# interface_01.net
KiCad netlist of a schematic drawn in EAGLE
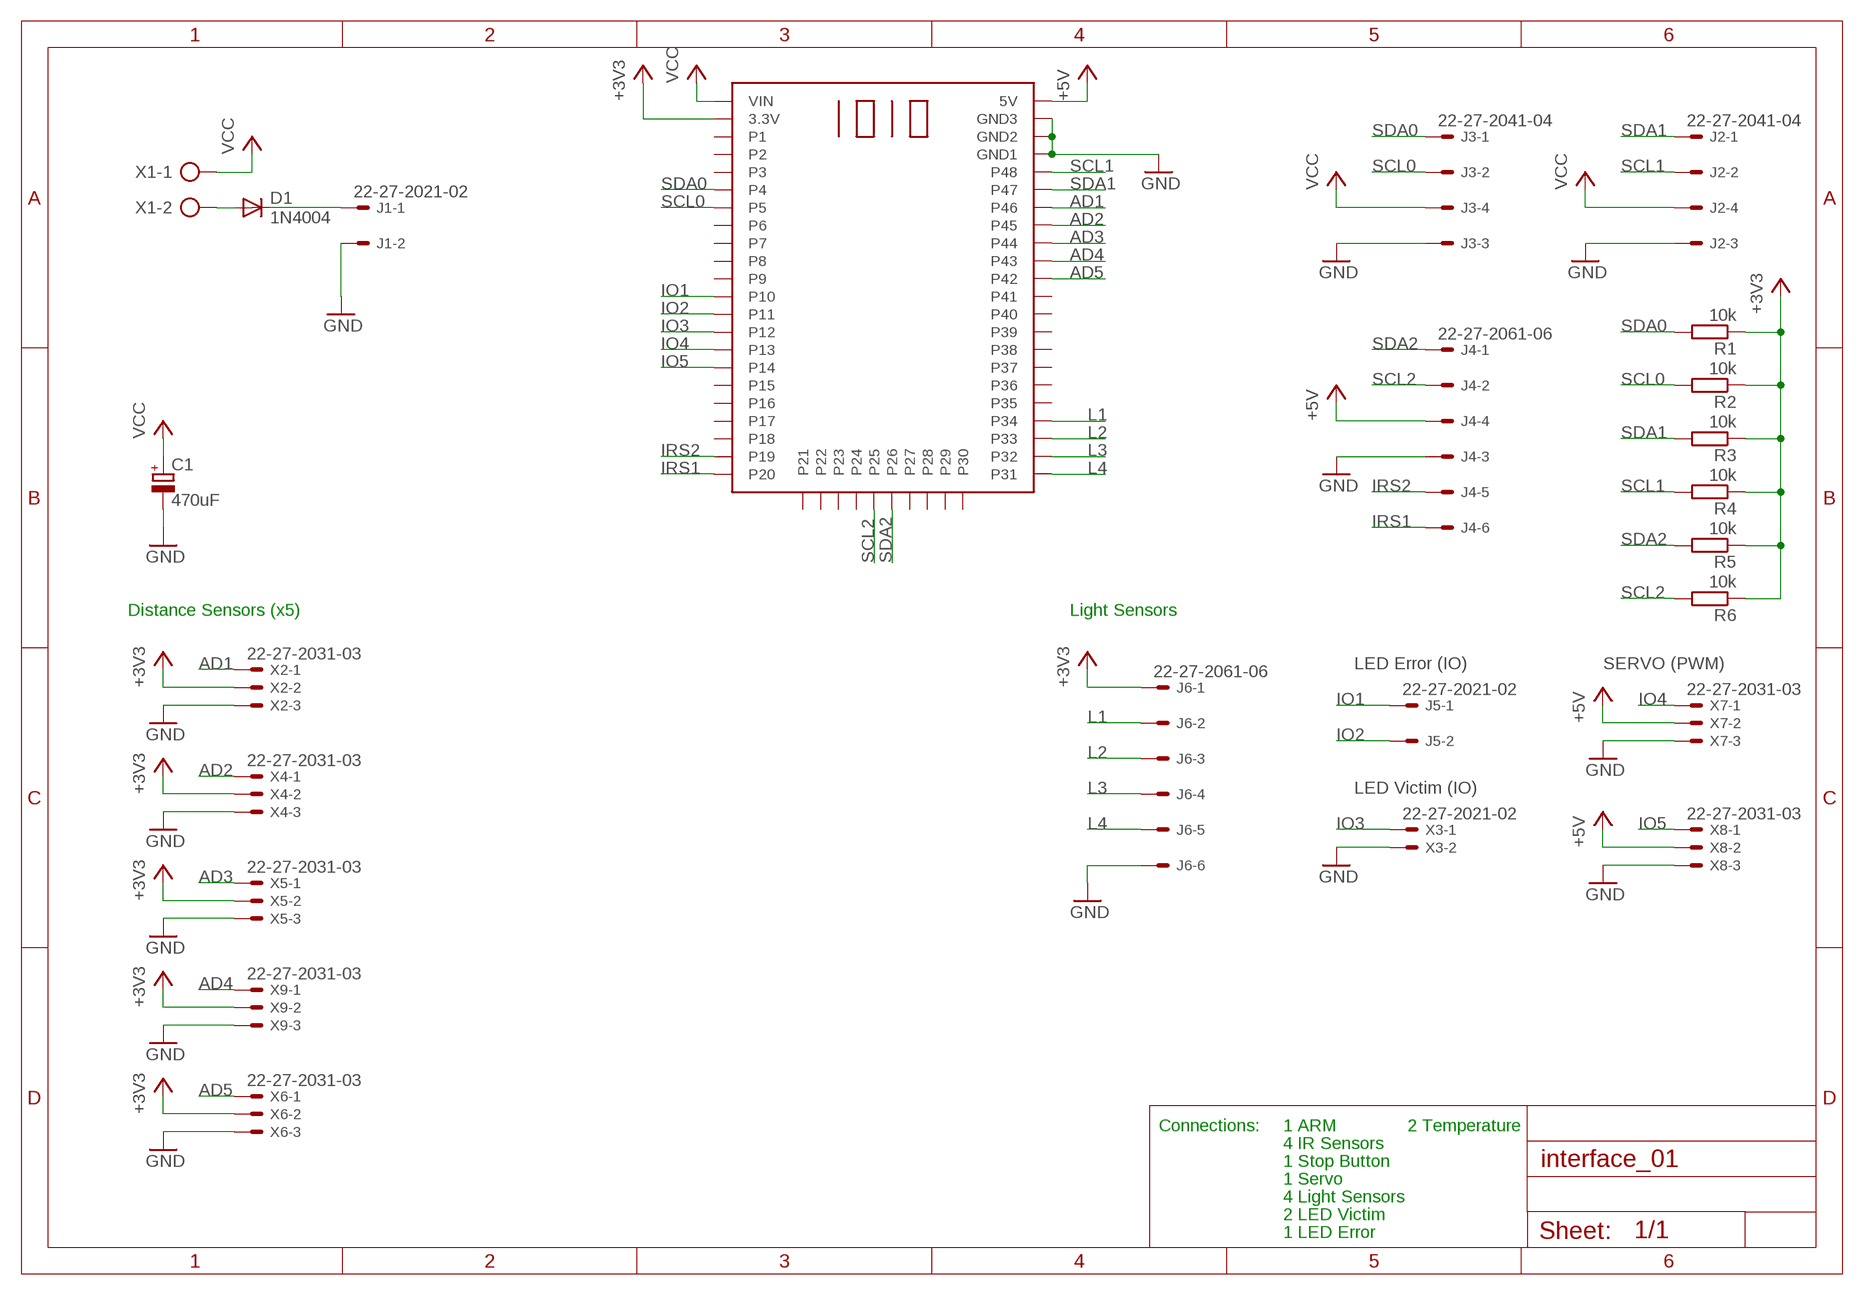
[diagram p0: schematic, sheet 1]

(export (version "E")
  (design (tool "Eeschema 10.0.6"))
  (components
    (comp (ref "C1")
      (value "470uF")
      (footprint "eagle-import:E5-10,5")
      (libsource (lib "eagle-import") (part "CPOL-EUE5-10.5"))
    )
    (comp (ref "D1")
      (value "1N4004")
      (footprint "eagle-import:DO41-10")
      (libsource (lib "eagle-import") (part "1N4004"))
    )
    (comp (ref "J1")
      (value "22-27-2021-02")
      (footprint "eagle-import:6410-02")
      (libsource (lib "eagle-import") (part "22-?-0227-2021"))
    )
    (comp (ref "J2")
      (value "22-27-2041-04")
      (footprint "eagle-import:6410-04")
      (libsource (lib "eagle-import") (part "22-?-0427-2041"))
    )
    (comp (ref "J3")
      (value "22-27-2041-04")
      (footprint "eagle-import:6410-04")
      (libsource (lib "eagle-import") (part "22-?-0427-2041"))
    )
    (comp (ref "J4")
      (value "22-27-2061-06")
      (footprint "eagle-import:6410-06")
      (libsource (lib "eagle-import") (part "22-?-0627-2061"))
    )
    (comp (ref "J5")
      (value "22-27-2021-02")
      (footprint "eagle-import:6410-02")
      (libsource (lib "eagle-import") (part "22-?-0227-2021"))
    )
    (comp (ref "J6")
      (value "22-27-2061-06")
      (footprint "eagle-import:6410-06")
      (libsource (lib "eagle-import") (part "22-?-0627-2061"))
    )
    (comp (ref "R1")
      (value "10k")
      (footprint "eagle-import:0204_7")
      (libsource (lib "eagle-import") (part "R-EU_0204/7"))
    )
    (comp (ref "R2")
      (value "10k")
      (footprint "eagle-import:0204_7")
      (libsource (lib "eagle-import") (part "R-EU_0204/7"))
    )
    (comp (ref "R3")
      (value "10k")
      (footprint "eagle-import:0204_7")
      (libsource (lib "eagle-import") (part "R-EU_0204/7"))
    )
    (comp (ref "R4")
      (value "10k")
      (footprint "eagle-import:0204_7")
      (libsource (lib "eagle-import") (part "R-EU_0204/7"))
    )
    (comp (ref "R5")
      (value "10k")
      (footprint "eagle-import:0204_7")
      (libsource (lib "eagle-import") (part "R-EU_0204/7"))
    )
    (comp (ref "R6")
      (value "10k")
      (footprint "eagle-import:0204_7")
      (libsource (lib "eagle-import") (part "R-EU_0204/7"))
    )
    (comp (ref "U$1")
      (value "IOIO")
      (footprint "eagle-import:IOIO")
      (libsource (lib "eagle-import") (part "IOIO"))
    )
    (comp (ref "X1")
      (value "AK500/2")
      (footprint "eagle-import:AK500_2")
      (libsource (lib "eagle-import") (part "AK500/2"))
    )
    (comp (ref "X2")
      (value "22-27-2031-03")
      (footprint "eagle-import:6410-03")
      (libsource (lib "eagle-import") (part "22-?-0327-2031"))
    )
    (comp (ref "X3")
      (value "22-27-2021-02")
      (footprint "eagle-import:6410-02")
      (libsource (lib "eagle-import") (part "22-?-0227-2021"))
    )
    (comp (ref "X4")
      (value "22-27-2031-03")
      (footprint "eagle-import:6410-03")
      (libsource (lib "eagle-import") (part "22-?-0327-2031"))
    )
    (comp (ref "X5")
      (value "22-27-2031-03")
      (footprint "eagle-import:6410-03")
      (libsource (lib "eagle-import") (part "22-?-0327-2031"))
    )
    (comp (ref "X6")
      (value "22-27-2031-03")
      (footprint "eagle-import:6410-03")
      (libsource (lib "eagle-import") (part "22-?-0327-2031"))
    )
    (comp (ref "X7")
      (value "22-27-2031-03")
      (footprint "eagle-import:6410-03")
      (libsource (lib "eagle-import") (part "22-?-0327-2031"))
    )
    (comp (ref "X8")
      (value "22-27-2031-03")
      (footprint "eagle-import:6410-03")
      (libsource (lib "eagle-import") (part "22-?-0327-2031"))
    )
    (comp (ref "X9")
      (value "22-27-2031-03")
      (footprint "eagle-import:6410-03")
      (libsource (lib "eagle-import") (part "22-?-0327-2031"))
    )
  )
  (nets
    (net (code "1") (name "+3V3") (class "Default")
      (node (ref "J6") (pin "1") (pinfunction "S_1") (pintype "passive"))
      (node (ref "R1") (pin "1") (pinfunction "1_1") (pintype "passive"))
      (node (ref "R2") (pin "1") (pinfunction "1_1") (pintype "passive"))
      (node (ref "R3") (pin "1") (pinfunction "1_1") (pintype "passive"))
      (node (ref "R4") (pin "1") (pinfunction "1_1") (pintype "passive"))
      (node (ref "R5") (pin "1") (pinfunction "1_1") (pintype "passive"))
      (node (ref "R6") (pin "1") (pinfunction "1_1") (pintype "passive"))
      (node (ref "U$1") (pin "P$2") (pinfunction "3.3V_P$2") (pintype "bidirectional"))
      (node (ref "X2") (pin "2") (pinfunction "S_2") (pintype "passive"))
      (node (ref "X4") (pin "2") (pinfunction "S_2") (pintype "passive"))
      (node (ref "X5") (pin "2") (pinfunction "S_2") (pintype "passive"))
      (node (ref "X6") (pin "2") (pinfunction "S_2") (pintype "passive"))
      (node (ref "X9") (pin "2") (pinfunction "S_2") (pintype "passive"))
    )
    (net (code "2") (name "+5V") (class "Default")
      (node (ref "J4") (pin "4") (pinfunction "S_4") (pintype "passive"))
      (node (ref "U$1") (pin "P$54") (pinfunction "5V_P$54") (pintype "bidirectional"))
      (node (ref "X7") (pin "2") (pinfunction "S_2") (pintype "passive"))
      (node (ref "X8") (pin "2") (pinfunction "S_2") (pintype "passive"))
    )
    (net (code "3") (name "/AD1") (class "Default")
      (node (ref "U$1") (pin "P$48") (pinfunction "P46_P$48") (pintype "bidirectional"))
      (node (ref "X2") (pin "1") (pinfunction "S_1") (pintype "passive"))
    )
    (net (code "4") (name "/AD2") (class "Default")
      (node (ref "U$1") (pin "P$47") (pinfunction "P45_P$47") (pintype "bidirectional"))
      (node (ref "X4") (pin "1") (pinfunction "S_1") (pintype "passive"))
    )
    (net (code "5") (name "/AD3") (class "Default")
      (node (ref "U$1") (pin "P$46") (pinfunction "P44_P$46") (pintype "bidirectional"))
      (node (ref "X5") (pin "1") (pinfunction "S_1") (pintype "passive"))
    )
    (net (code "6") (name "/AD4") (class "Default")
      (node (ref "U$1") (pin "P$45") (pinfunction "P43_P$45") (pintype "bidirectional"))
      (node (ref "X9") (pin "1") (pinfunction "S_1") (pintype "passive"))
    )
    (net (code "7") (name "/AD5") (class "Default")
      (node (ref "U$1") (pin "P$44") (pinfunction "P42_P$44") (pintype "bidirectional"))
      (node (ref "X6") (pin "1") (pinfunction "S_1") (pintype "passive"))
    )
    (net (code "8") (name "/IO1") (class "Default")
      (node (ref "J5") (pin "1") (pinfunction "S_1") (pintype "passive"))
      (node (ref "U$1") (pin "P$12") (pinfunction "P10_P$12") (pintype "bidirectional"))
    )
    (net (code "9") (name "/IO2") (class "Default")
      (node (ref "J5") (pin "2") (pinfunction "S_2") (pintype "passive"))
      (node (ref "U$1") (pin "P$13") (pinfunction "P11_P$13") (pintype "bidirectional"))
    )
    (net (code "10") (name "/IO3") (class "Default")
      (node (ref "U$1") (pin "P$14") (pinfunction "P12_P$14") (pintype "bidirectional"))
      (node (ref "X3") (pin "1") (pinfunction "S_1") (pintype "passive"))
    )
    (net (code "11") (name "/IO4") (class "Default")
      (node (ref "U$1") (pin "P$15") (pinfunction "P13_P$15") (pintype "bidirectional"))
      (node (ref "X7") (pin "1") (pinfunction "S_1") (pintype "passive"))
    )
    (net (code "12") (name "/IO5") (class "Default")
      (node (ref "U$1") (pin "P$16") (pinfunction "P14_P$16") (pintype "bidirectional"))
      (node (ref "X8") (pin "1") (pinfunction "S_1") (pintype "passive"))
    )
    (net (code "13") (name "/IRS1") (class "Default")
      (node (ref "J4") (pin "6") (pinfunction "S_6") (pintype "passive"))
      (node (ref "U$1") (pin "P$22") (pinfunction "P20_P$22") (pintype "bidirectional"))
    )
    (net (code "14") (name "/IRS2") (class "Default")
      (node (ref "J4") (pin "5") (pinfunction "S_5") (pintype "passive"))
      (node (ref "U$1") (pin "P$21") (pinfunction "P19_P$21") (pintype "bidirectional"))
    )
    (net (code "15") (name "/L1") (class "Default")
      (node (ref "J6") (pin "2") (pinfunction "S_2") (pintype "passive"))
      (node (ref "U$1") (pin "P$36") (pinfunction "P34_P$36") (pintype "bidirectional"))
    )
    (net (code "16") (name "/L2") (class "Default")
      (node (ref "J6") (pin "3") (pinfunction "S_3") (pintype "passive"))
      (node (ref "U$1") (pin "P$35") (pinfunction "P33_P$35") (pintype "bidirectional"))
    )
    (net (code "17") (name "/L3") (class "Default")
      (node (ref "J6") (pin "4") (pinfunction "S_4") (pintype "passive"))
      (node (ref "U$1") (pin "P$34") (pinfunction "P32_P$34") (pintype "bidirectional"))
    )
    (net (code "18") (name "/L4") (class "Default")
      (node (ref "J6") (pin "5") (pinfunction "S_5") (pintype "passive"))
      (node (ref "U$1") (pin "P$33") (pinfunction "P31_P$33") (pintype "bidirectional"))
    )
    (net (code "19") (name "/SCL0") (class "Default")
      (node (ref "J3") (pin "2") (pinfunction "S_2") (pintype "passive"))
      (node (ref "R2") (pin "2") (pinfunction "2_2") (pintype "passive"))
      (node (ref "U$1") (pin "P$7") (pinfunction "P5_P$7") (pintype "bidirectional"))
    )
    (net (code "20") (name "/SCL1") (class "Default")
      (node (ref "J2") (pin "2") (pinfunction "S_2") (pintype "passive"))
      (node (ref "R4") (pin "2") (pinfunction "2_2") (pintype "passive"))
      (node (ref "U$1") (pin "P$50") (pinfunction "P48_P$50") (pintype "bidirectional"))
    )
    (net (code "21") (name "/SCL2") (class "Default")
      (node (ref "J4") (pin "2") (pinfunction "S_2") (pintype "passive"))
      (node (ref "R6") (pin "2") (pinfunction "2_2") (pintype "passive"))
      (node (ref "U$1") (pin "P$27") (pinfunction "P25_P$27") (pintype "bidirectional"))
    )
    (net (code "22") (name "/SDA0") (class "Default")
      (node (ref "J3") (pin "1") (pinfunction "S_1") (pintype "passive"))
      (node (ref "R1") (pin "2") (pinfunction "2_2") (pintype "passive"))
      (node (ref "U$1") (pin "P$6") (pinfunction "P4_P$6") (pintype "bidirectional"))
    )
    (net (code "23") (name "/SDA1") (class "Default")
      (node (ref "J2") (pin "1") (pinfunction "S_1") (pintype "passive"))
      (node (ref "R3") (pin "2") (pinfunction "2_2") (pintype "passive"))
      (node (ref "U$1") (pin "P$49") (pinfunction "P47_P$49") (pintype "bidirectional"))
    )
    (net (code "24") (name "/SDA2") (class "Default")
      (node (ref "J4") (pin "1") (pinfunction "S_1") (pintype "passive"))
      (node (ref "R5") (pin "2") (pinfunction "2_2") (pintype "passive"))
      (node (ref "U$1") (pin "P$28") (pinfunction "P26_P$28") (pintype "bidirectional"))
    )
    (net (code "25") (name "GND") (class "Default")
      (node (ref "C1") (pin "-") (pinfunction "-_-") (pintype "passive"))
      (node (ref "J1") (pin "2") (pinfunction "S_2") (pintype "passive"))
      (node (ref "J2") (pin "3") (pinfunction "S_3") (pintype "passive"))
      (node (ref "J3") (pin "3") (pinfunction "S_3") (pintype "passive"))
      (node (ref "J4") (pin "3") (pinfunction "S_3") (pintype "passive"))
      (node (ref "J6") (pin "6") (pinfunction "S_6") (pintype "passive"))
      (node (ref "U$1") (pin "P$51") (pinfunction "GND1_P$51") (pintype "bidirectional"))
      (node (ref "U$1") (pin "P$52") (pinfunction "GND2_P$52") (pintype "bidirectional"))
      (node (ref "U$1") (pin "P$53") (pinfunction "GND3_P$53") (pintype "bidirectional"))
      (node (ref "X2") (pin "3") (pinfunction "S_3") (pintype "passive"))
      (node (ref "X3") (pin "2") (pinfunction "S_2") (pintype "passive"))
      (node (ref "X4") (pin "3") (pinfunction "S_3") (pintype "passive"))
      (node (ref "X5") (pin "3") (pinfunction "S_3") (pintype "passive"))
      (node (ref "X6") (pin "3") (pinfunction "S_3") (pintype "passive"))
      (node (ref "X7") (pin "3") (pinfunction "S_3") (pintype "passive"))
      (node (ref "X8") (pin "3") (pinfunction "S_3") (pintype "passive"))
      (node (ref "X9") (pin "3") (pinfunction "S_3") (pintype "passive"))
    )
    (net (code "26") (name "Net-(J1A-S)") (class "Default")
      (node (ref "D1") (pin "C") (pinfunction "C_C") (pintype "passive"))
      (node (ref "J1") (pin "1") (pinfunction "S_1") (pintype "passive"))
    )
    (net (code "27") (name "Net-(X1B-KL)") (class "Default")
      (node (ref "D1") (pin "A") (pinfunction "A_A") (pintype "passive"))
      (node (ref "X1") (pin "2") (pinfunction "KL_2") (pintype "passive"))
    )
    (net (code "28") (name "VCC") (class "Default")
      (node (ref "C1") (pin "+") (pinfunction "+_+") (pintype "passive"))
      (node (ref "J2") (pin "4") (pinfunction "S_4") (pintype "passive"))
      (node (ref "J3") (pin "4") (pinfunction "S_4") (pintype "passive"))
      (node (ref "U$1") (pin "P$1") (pinfunction "VIN_P$1") (pintype "bidirectional"))
      (node (ref "X1") (pin "1") (pinfunction "KL_1") (pintype "passive"))
    )
    (net (code "29") (name "unconnected-(U$1-P1-PadP$3)") (class "Default")
      (node (ref "U$1") (pin "P$3") (pinfunction "P1_P$3") (pintype "bidirectional"))
    )
    (net (code "30") (name "unconnected-(U$1-P2-PadP$4)") (class "Default")
      (node (ref "U$1") (pin "P$4") (pinfunction "P2_P$4") (pintype "bidirectional"))
    )
    (net (code "31") (name "unconnected-(U$1-P3-PadP$5)") (class "Default")
      (node (ref "U$1") (pin "P$5") (pinfunction "P3_P$5") (pintype "bidirectional"))
    )
    (net (code "32") (name "unconnected-(U$1-P6-PadP$8)") (class "Default")
      (node (ref "U$1") (pin "P$8") (pinfunction "P6_P$8") (pintype "bidirectional"))
    )
    (net (code "33") (name "unconnected-(U$1-P7-PadP$9)") (class "Default")
      (node (ref "U$1") (pin "P$9") (pinfunction "P7_P$9") (pintype "bidirectional"))
    )
    (net (code "34") (name "unconnected-(U$1-P8-PadP$10)") (class "Default")
      (node (ref "U$1") (pin "P$10") (pinfunction "P8_P$10") (pintype "bidirectional"))
    )
    (net (code "35") (name "unconnected-(U$1-P9-PadP$11)") (class "Default")
      (node (ref "U$1") (pin "P$11") (pinfunction "P9_P$11") (pintype "bidirectional"))
    )
    (net (code "36") (name "unconnected-(U$1-P15-PadP$17)") (class "Default")
      (node (ref "U$1") (pin "P$17") (pinfunction "P15_P$17") (pintype "bidirectional"))
    )
    (net (code "37") (name "unconnected-(U$1-P16-PadP$18)") (class "Default")
      (node (ref "U$1") (pin "P$18") (pinfunction "P16_P$18") (pintype "bidirectional"))
    )
    (net (code "38") (name "unconnected-(U$1-P17-PadP$19)") (class "Default")
      (node (ref "U$1") (pin "P$19") (pinfunction "P17_P$19") (pintype "bidirectional"))
    )
    (net (code "39") (name "unconnected-(U$1-P18-PadP$20)") (class "Default")
      (node (ref "U$1") (pin "P$20") (pinfunction "P18_P$20") (pintype "bidirectional"))
    )
    (net (code "40") (name "unconnected-(U$1-P21-PadP$23)") (class "Default")
      (node (ref "U$1") (pin "P$23") (pinfunction "P21_P$23") (pintype "bidirectional"))
    )
    (net (code "41") (name "unconnected-(U$1-P22-PadP$24)") (class "Default")
      (node (ref "U$1") (pin "P$24") (pinfunction "P22_P$24") (pintype "bidirectional"))
    )
    (net (code "42") (name "unconnected-(U$1-P23-PadP$25)") (class "Default")
      (node (ref "U$1") (pin "P$25") (pinfunction "P23_P$25") (pintype "bidirectional"))
    )
    (net (code "43") (name "unconnected-(U$1-P24-PadP$26)") (class "Default")
      (node (ref "U$1") (pin "P$26") (pinfunction "P24_P$26") (pintype "bidirectional"))
    )
    (net (code "44") (name "unconnected-(U$1-P27-PadP$29)") (class "Default")
      (node (ref "U$1") (pin "P$29") (pinfunction "P27_P$29") (pintype "bidirectional"))
    )
    (net (code "45") (name "unconnected-(U$1-P28-PadP$30)") (class "Default")
      (node (ref "U$1") (pin "P$30") (pinfunction "P28_P$30") (pintype "bidirectional"))
    )
    (net (code "46") (name "unconnected-(U$1-P29-PadP$31)") (class "Default")
      (node (ref "U$1") (pin "P$31") (pinfunction "P29_P$31") (pintype "bidirectional"))
    )
    (net (code "47") (name "unconnected-(U$1-P30-PadP$32)") (class "Default")
      (node (ref "U$1") (pin "P$32") (pinfunction "P30_P$32") (pintype "bidirectional"))
    )
    (net (code "48") (name "unconnected-(U$1-P35-PadP$37)") (class "Default")
      (node (ref "U$1") (pin "P$37") (pinfunction "P35_P$37") (pintype "bidirectional"))
    )
    (net (code "49") (name "unconnected-(U$1-P36-PadP$38)") (class "Default")
      (node (ref "U$1") (pin "P$38") (pinfunction "P36_P$38") (pintype "bidirectional"))
    )
    (net (code "50") (name "unconnected-(U$1-P37-PadP$39)") (class "Default")
      (node (ref "U$1") (pin "P$39") (pinfunction "P37_P$39") (pintype "bidirectional"))
    )
    (net (code "51") (name "unconnected-(U$1-P38-PadP$40)") (class "Default")
      (node (ref "U$1") (pin "P$40") (pinfunction "P38_P$40") (pintype "bidirectional"))
    )
    (net (code "52") (name "unconnected-(U$1-P39-PadP$41)") (class "Default")
      (node (ref "U$1") (pin "P$41") (pinfunction "P39_P$41") (pintype "bidirectional"))
    )
    (net (code "53") (name "unconnected-(U$1-P40-PadP$42)") (class "Default")
      (node (ref "U$1") (pin "P$42") (pinfunction "P40_P$42") (pintype "bidirectional"))
    )
    (net (code "54") (name "unconnected-(U$1-P41-PadP$43)") (class "Default")
      (node (ref "U$1") (pin "P$43") (pinfunction "P41_P$43") (pintype "bidirectional"))
    )
  )
)
